# ESP32_USB_C.net
KiCad netlist of a schematic drawn in Altium Designer
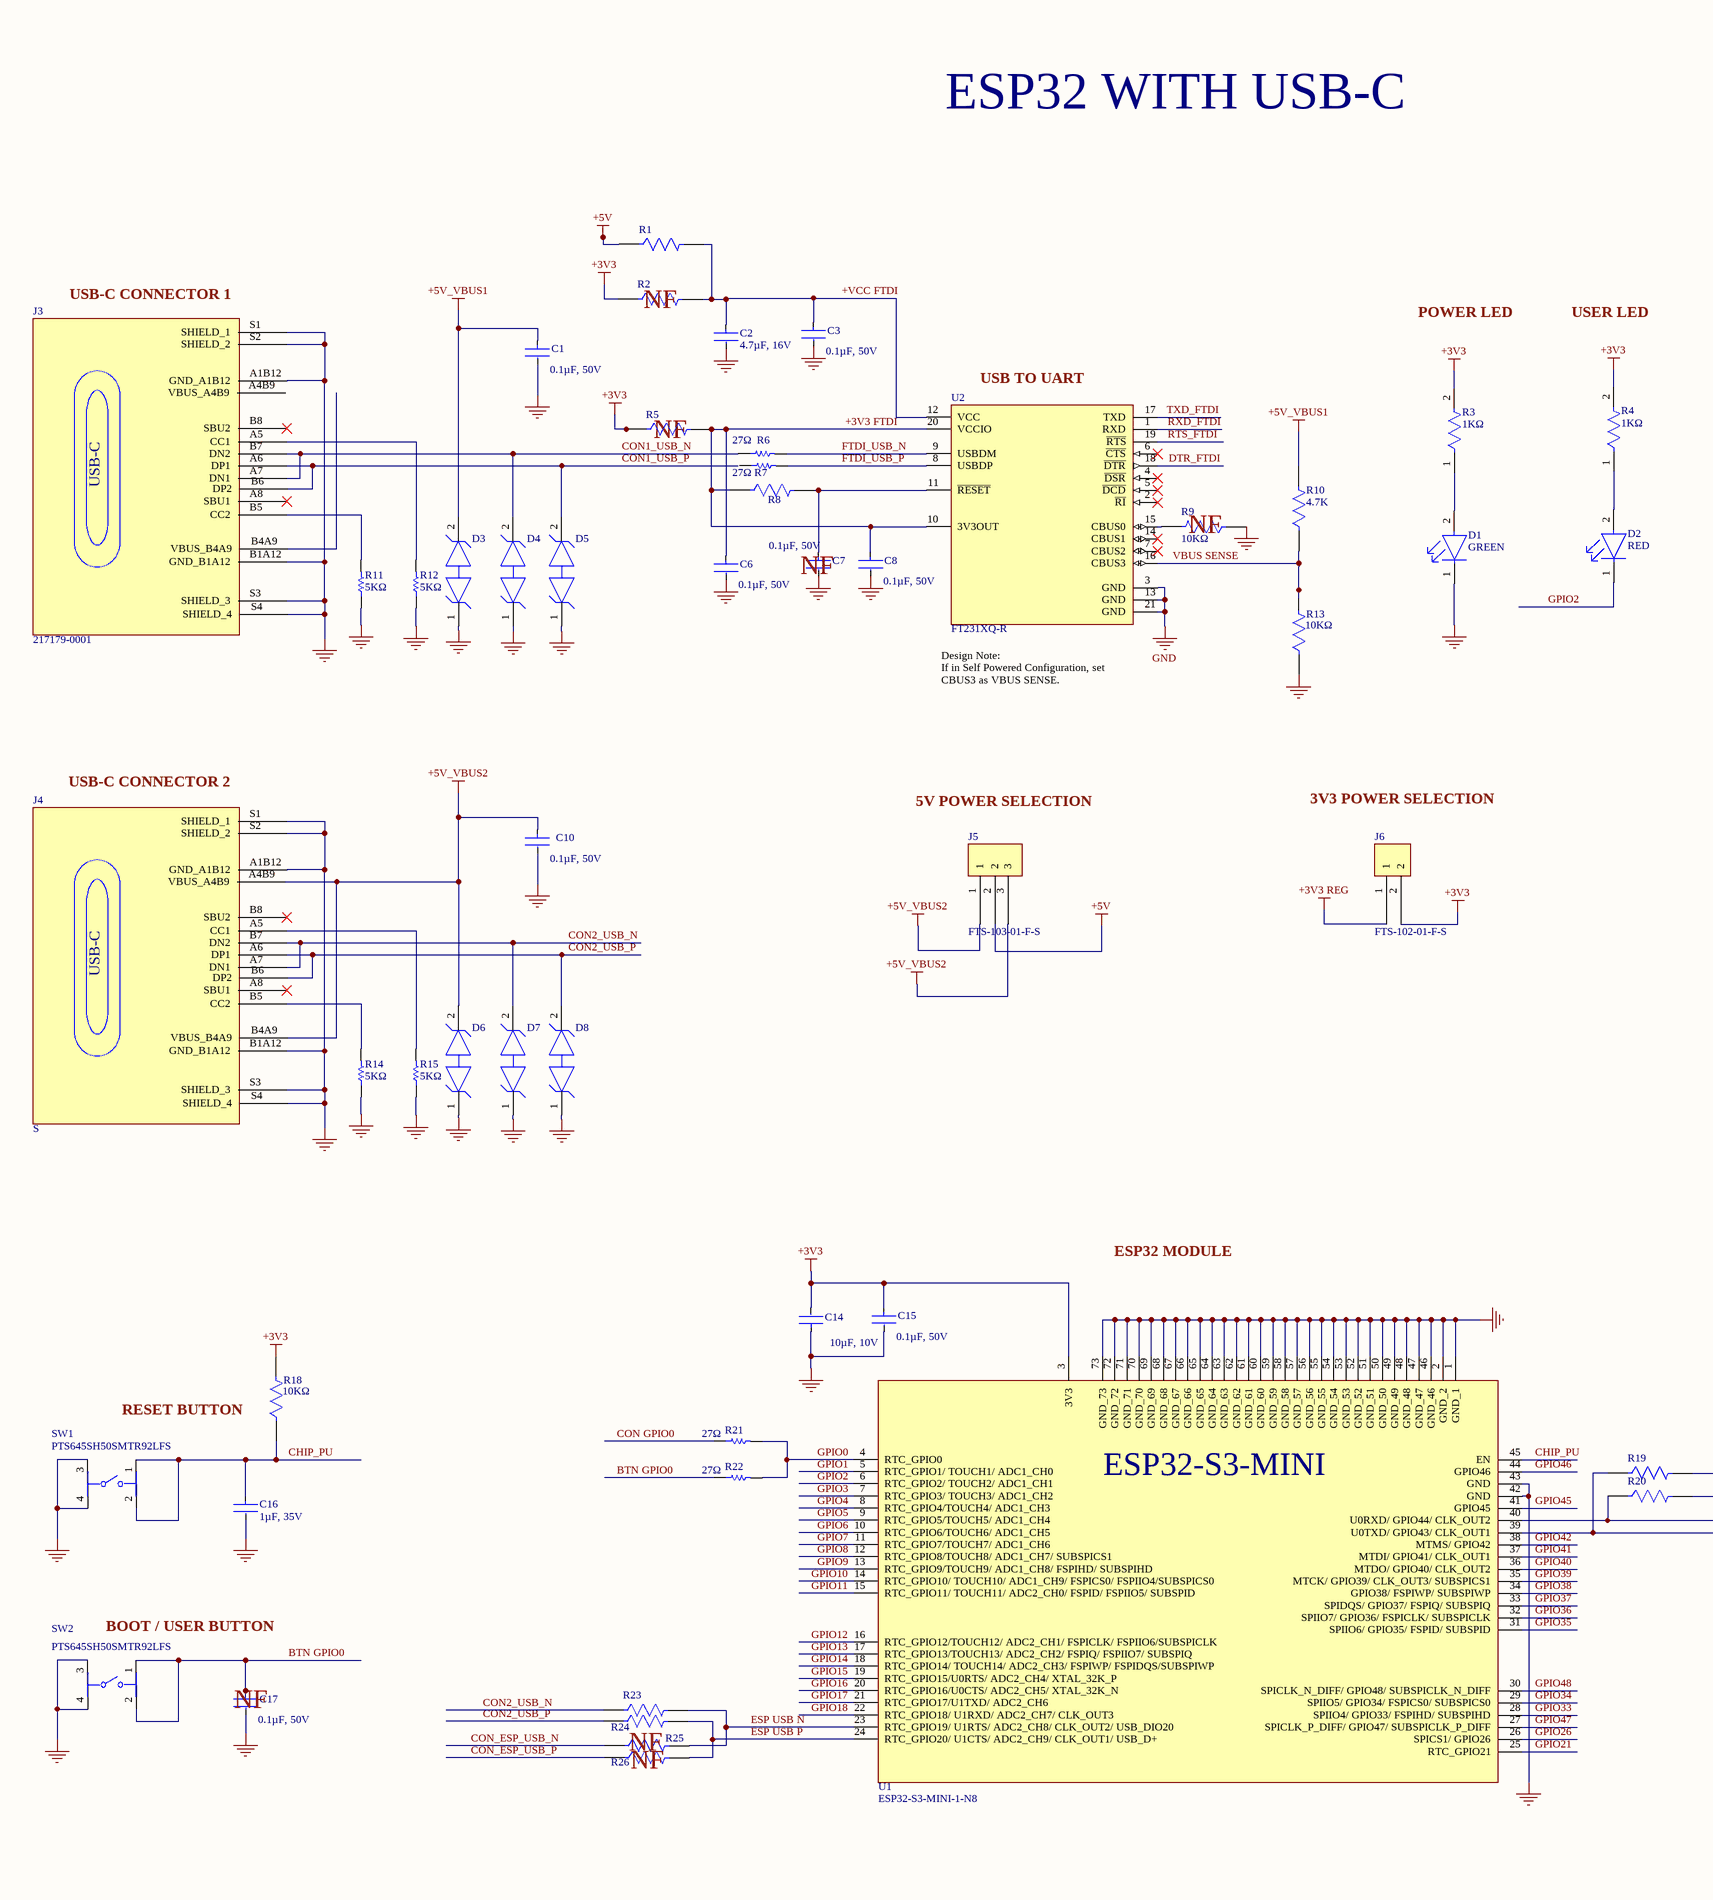
[diagram p0: ESP32_USB_C.SchDoc, left]
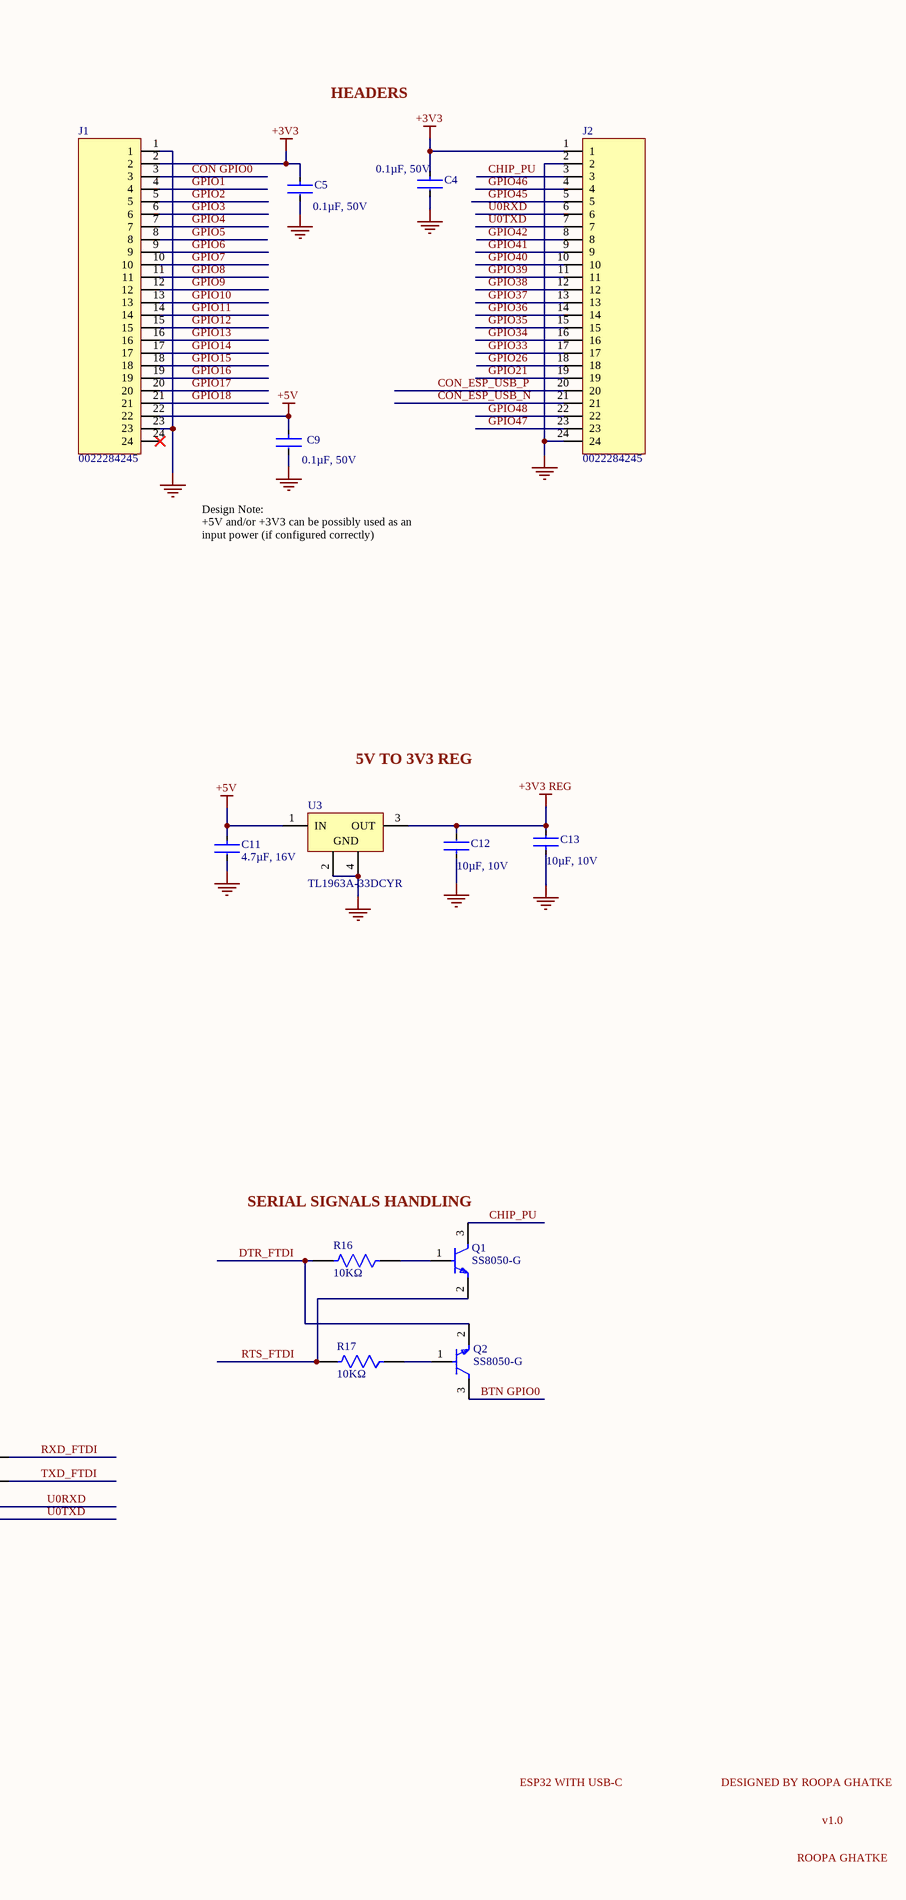
[diagram p1: ESP32_USB_C.SchDoc, right]

(export (version "E")
  (design (tool "Eeschema 10.0.6"))
  (components
    (comp (ref "C1")
      (value "0.1µF, 50V")
      (footprint "FP-CL779-IPC_C")
      (description "Cap Ceramic 100nF 50V X7R ±10% SMD 0402 +125°C Paper T/R")
      (libsource (lib "") (part "b4654b650e69147ec39a6b967a45e02_2"))
    )
    (comp (ref "C2")
      (value "4.7µF, 16V")
      (footprint "FP-CL829-IPC_C")
      (description "Cap Ceramic 4.7uF 16V X5R ±20% SMD 0402 +85°C Paper T/R")
      (fields (field (name "TOLERANCE") "20%"))
      (libsource (lib "Altium Content Vault") (part "b4654b650e69147ec39a6b967a45e02"))
    )
    (comp (ref "C3")
      (value "0.1µF, 50V")
      (footprint "FP-CL779-IPC_C")
      (description "Cap Ceramic 100nF 50V X7R ±10% SMD 0402 +125°C Paper T/R")
      (libsource (lib "Altium Content Vault") (part "b4654b650e69147ec39a6b967a45e02"))
    )
    (comp (ref "C4")
      (value "0.1µF, 50V")
      (footprint "FP-CL779-IPC_C")
      (description "Cap Ceramic 100nF 50V X7R ±10% SMD 0402 +125°C Paper T/R")
      (libsource (lib "") (part "b4654b650e69147ec39a6b967a45e02_1"))
    )
    (comp (ref "C5")
      (value "0.1µF, 50V")
      (footprint "FP-CL779-IPC_C")
      (description "Cap Ceramic 100nF 50V X7R ±10% SMD 0402 +125°C Paper T/R")
      (libsource (lib "Altium Content Vault") (part "b4654b650e69147ec39a6b967a45e02"))
    )
    (comp (ref "C6")
      (value "0.1µF, 50V")
      (footprint "FP-CL779-IPC_C")
      (description "Cap Ceramic 100nF 50V X7R ±10% SMD 0402 +125°C Paper T/R")
      (libsource (lib "Altium Content Vault") (part "b4654b650e69147ec39a6b967a45e02"))
    )
    (comp (ref "C7")
      (value "0.1µF, 50V")
      (footprint "FP-CL779-IPC_C")
      (description "Cap Ceramic 100nF 50V X7R ±10% SMD 0402 +125°C Paper T/R")
      (libsource (lib "Altium Content Vault") (part "b4654b650e69147ec39a6b967a45e02"))
    )
    (comp (ref "C8")
      (value "0.1µF, 50V")
      (footprint "FP-CL779-IPC_C")
      (description "Cap Ceramic 100nF 50V X7R ±10% SMD 0402 +125°C Paper T/R")
      (libsource (lib "Altium Content Vault") (part "b4654b650e69147ec39a6b967a45e02"))
    )
    (comp (ref "C9")
      (value "0.1µF, 50V")
      (footprint "FP-CL779-IPC_C")
      (description "Cap Ceramic 100nF 50V X7R ±10% SMD 0402 +125°C Paper T/R")
      (libsource (lib "Altium Content Vault") (part "b4654b650e69147ec39a6b967a45e02"))
    )
    (comp (ref "C10")
      (value "0.1µF, 50V")
      (footprint "FP-CL779-IPC_C")
      (description "Cap Ceramic 100nF 50V X7R ±10% SMD 0402 +125°C Paper T/R")
      (libsource (lib "Altium Content Vault") (part "b4654b650e69147ec39a6b967a45e02"))
    )
    (comp (ref "C11")
      (value "4.7µF, 16V")
      (footprint "FP-CL829-IPC_C")
      (description "Cap Ceramic 4.7uF 16V X5R ±20% SMD 0402 +85°C Paper T/R")
      (fields (field (name "TOLERANCE") "20%"))
      (libsource (lib "Altium Content Vault") (part "b4654b650e69147ec39a6b967a45e02"))
    )
    (comp (ref "C12")
      (value "10µF, 10V")
      (footprint "FP-CL07-IPC_C")
      (description "Cap Ceramic 10uF 10V X5R ±20% SMD 0402 +85°C Paper T/R")
      (fields (field (name "TOLERANCE") "20%"))
      (libsource (lib "Altium Content Vault") (part "b4654b650e69147ec39a6b967a45e02"))
    )
    (comp (ref "C13")
      (value "10µF, 10V")
      (footprint "FP-CL07-IPC_C")
      (description "Cap Ceramic 10uF 10V X5R ±20% SMD 0402 +85°C Paper T/R")
      (fields (field (name "TOLERANCE") "20%"))
      (libsource (lib "Altium Content Vault") (part "b4654b650e69147ec39a6b967a45e02"))
    )
    (comp (ref "C14")
      (value "10µF, 10V")
      (footprint "FP-CL07-IPC_C")
      (description "Cap Ceramic 10uF 10V X5R ±20% SMD 0402 +85°C Paper T/R")
      (fields (field (name "TOLERANCE") "20%"))
      (libsource (lib "Altium Content Vault") (part "b4654b650e69147ec39a6b967a45e02"))
    )
    (comp (ref "C15")
      (value "0.1µF, 50V")
      (footprint "FP-CL779-IPC_C")
      (description "Cap Ceramic 100nF 50V X7R ±10% SMD 0402 +125°C Paper T/R")
      (libsource (lib "Altium Content Vault") (part "b4654b650e69147ec39a6b967a45e02"))
    )
    (comp (ref "C16")
      (value "1µF, 35V")
      (footprint "FP-CL440-IPC_C")
      (description "Cap Ceramic 1uF 35V X5R ±10% SMD 0402 +85°C Paper T/R")
      (fields (field (name "TOLERANCE") "10%"))
      (libsource (lib "Altium Content Vault") (part "b4654b650e69147ec39a6b967a45e02"))
    )
    (comp (ref "C17")
      (value "0.1µF, 50V")
      (footprint "FP-CL779-IPC_C")
      (description "Cap Ceramic 100nF 50V X7R ±10% SMD 0402 +125°C Paper T/R")
      (libsource (lib "Altium Content Vault") (part "b4654b650e69147ec39a6b967a45e02"))
    )
    (comp (ref "D1")
      (value "GREEN")
      (footprint "FP-6_541-5056_01-4-MFG")
      (description "LED GREEN 0603 SMD")
      (fields
        (field (name "MANUFACTURER PART NUMBER") "TLMP1100-GS08")
        (field (name "MANUFACTURER") "Vishay")
      )
      (libsource (lib "Altium Content Vault") (part "8706943c75ba83719d021d2fdc84c58"))
    )
    (comp (ref "D2")
      (value "RED")
      (footprint "FP-SML-P1-MFG")
      (description "LED RED CLEAR 0402 SMD")
      (fields
        (field (name "OCTOPART") "https://octopart.com/sml-p12vtt86r-rohm-34112315")
        (field (name "MANUFACTURER") "Rohm")
      )
      (libsource (lib "Altium Content Vault") (part "8706943c75ba83719d021d2fdc84c58"))
    )
    (comp (ref "D3")
      (value "SD36C-01FTG")
      (footprint "FP-SD-C-MFG")
      (description "TVS DIODE 36V 60V SOD323")
      (fields
        (field (name "OCTOPART") "https://octopart.com/sd36c-01ftg-littelfuse-46949624")
        (field (name "MANUFACTURER") "Littelfuse")
      )
      (libsource (lib "Altium Content Vault") (part "5416617ffa6bd5ace45e61cf09a9423"))
    )
    (comp (ref "D4")
      (value "SD36C-01FTG")
      (footprint "FP-SD-C-MFG")
      (description "TVS DIODE 36V 60V SOD323")
      (fields
        (field (name "OCTOPART") "https://octopart.com/sd36c-01ftg-littelfuse-46949624")
        (field (name "MANUFACTURER") "Littelfuse")
      )
      (libsource (lib "Altium Content Vault") (part "5416617ffa6bd5ace45e61cf09a9423"))
    )
    (comp (ref "D5")
      (value "SD36C-01FTG")
      (footprint "FP-SD-C-MFG")
      (description "TVS DIODE 36V 60V SOD323")
      (fields
        (field (name "OCTOPART") "https://octopart.com/sd36c-01ftg-littelfuse-46949624")
        (field (name "MANUFACTURER") "Littelfuse")
      )
      (libsource (lib "Altium Content Vault") (part "5416617ffa6bd5ace45e61cf09a9423"))
    )
    (comp (ref "D6")
      (value "SD36C-01FTG")
      (footprint "FP-SD-C-MFG")
      (description "TVS DIODE 36V 60V SOD323")
      (fields
        (field (name "OCTOPART") "https://octopart.com/sd36c-01ftg-littelfuse-46949624")
        (field (name "MANUFACTURER") "Littelfuse")
      )
      (libsource (lib "Altium Content Vault") (part "5416617ffa6bd5ace45e61cf09a9423"))
    )
    (comp (ref "D7")
      (value "SD36C-01FTG")
      (footprint "FP-SD-C-MFG")
      (description "TVS DIODE 36V 60V SOD323")
      (fields
        (field (name "OCTOPART") "https://octopart.com/sd36c-01ftg-littelfuse-46949624")
        (field (name "MANUFACTURER") "Littelfuse")
      )
      (libsource (lib "Altium Content Vault") (part "5416617ffa6bd5ace45e61cf09a9423"))
    )
    (comp (ref "D8")
      (value "SD36C-01FTG")
      (footprint "FP-SD-C-MFG")
      (description "TVS DIODE 36V 60V SOD323")
      (fields
        (field (name "OCTOPART") "https://octopart.com/sd36c-01ftg-littelfuse-46949624")
        (field (name "MANUFACTURER") "Littelfuse")
      )
      (libsource (lib "Altium Content Vault") (part "5416617ffa6bd5ace45e61cf09a9423"))
    )
    (comp (ref "J1")
      (value "0022284245")
      (footprint "HRD_1X24_2.54MM")
      (description "CONN HEADER VERT 24POS 2.54MM")
      (fields (field (name "MANUFACTURER") "Molex") (field (name "MANUFACTURER PART NUMBER") "22-28-4245"))
      (libsource (lib "") (part "0022284245_1"))
    )
    (comp (ref "J2")
      (value "0022284245")
      (footprint "HRD_1X24_2.54MM")
      (description "CONN HEADER VERT 24POS 2.54MM")
      (fields (field (name "MANUFACTURER") "Molex") (field (name "MANUFACTURER PART NUMBER") "22-28-4245"))
      (libsource (lib "Schlib") (part "0022284245"))
    )
    (comp (ref "J3")
      (value "217179-0001")
      (footprint "MOLEX_2171790001")
      (description "USB Connector, USB Type C, USB 2.0, Receptacle, 16 Ways, Surface Mount, Through Hole Mount")
      (fields (field (name "MANUFACTURER") "Molex") (field (name "LCSC PART NUMBER") "C3197684"))
      (libsource (lib "Schlib") (part "217179-0001"))
    )
    (comp (ref "J4")
      (value "S")
      (footprint "MOLEX_2171790001")
      (description "USB Connector, USB Type C, USB 2.0, Receptacle, 16 Ways, Surface Mount, Through Hole Mount")
      (fields (field (name "MANUFACTURER") "Molex") (field (name "MANUFACTURER PART NUMBER") "217179-0001"))
      (libsource (lib "Schlib") (part "217179-0001"))
    )
    (comp (ref "J5")
      (value "FTS-103-01-F-S")
      (footprint "HRD_1X3_1.27MM")
      (description "CONN HEADER VERT 3POS 1.27MM")
      (fields (field (name "LCSC PART NUMBER") "C3333578"))
      (libsource (lib "Schlib") (part "FTS-103-01-F-S"))
    )
    (comp (ref "J6")
      (value "FTS-102-01-F-S")
      (footprint "HRD_1X2_1.27MM")
      (description "CONN HEADER VERT 2POS 1.27MM")
      (fields (field (name "LCSC PART NUMBER") "C3333578"))
      (libsource (lib "Schlib") (part "FTS-102-01-F-S"))
    )
    (comp (ref "Q1")
      (value "SS8050-G")
      (footprint "FP-SS8050-G-MFG")
      (description "NPN TRANSISTOR 1.5A 40V SOT-23 R")
      (libsource (lib "Altium Content Vault") (part "2a1388f82443b098dcd57d24ac7632d"))
    )
    (comp (ref "Q2")
      (value "SS8050-G")
      (footprint "FP-SS8050-G-MFG")
      (description "NPN TRANSISTOR 1.5A 40V SOT-23 R")
      (libsource (lib "Altium Content Vault") (part "2a1388f82443b098dcd57d24ac7632d"))
    )
    (comp (ref "R1")
      (value "RC0402FR-070RL")
      (footprint "FP-RC0402-0_4-IPC_A")
      (description "RES SMD 0 OHM JUMPER 1/16W 0402")
      (fields (field (name "TOLERANCE") "1%"))
      (libsource (lib "Altium Content Vault") (part "1029c3af85768c4190bb7ad29bc67b5"))
    )
    (comp (ref "R2")
      (value "RC0402FR-070RL")
      (footprint "FP-RC0402-0_4-IPC_A")
      (description "RES SMD 0 OHM JUMPER 1/16W 0402")
      (fields (field (name "TOLERANCE") "1%"))
      (libsource (lib "Altium Content Vault") (part "1029c3af85768c4190bb7ad29bc67b5"))
    )
    (comp (ref "R3")
      (value "1KΩ")
      (footprint "FP-RC0402-0_4-IPC_A")
      (description "RES 1K OHM 1% 1/16W 0402")
      (fields (field (name "TOLERANCE") "1%"))
      (libsource (lib "") (part "1029c3af85768c4190bb7ad29bc67b5_1"))
    )
    (comp (ref "R4")
      (value "1KΩ")
      (footprint "FP-RC0402-0_4-IPC_A")
      (description "RES 1K OHM 1% 1/16W 0402")
      (fields (field (name "TOLERANCE") "1%"))
      (libsource (lib "") (part "1029c3af85768c4190bb7ad29bc67b5_1"))
    )
    (comp (ref "R5")
      (value "RC0402FR-070RL")
      (footprint "FP-RC0402-0_4-IPC_A")
      (description "RES SMD 0 OHM JUMPER 1/16W 0402")
      (fields (field (name "TOLERANCE") "1%"))
      (libsource (lib "Altium Content Vault") (part "1029c3af85768c4190bb7ad29bc67b5"))
    )
    (comp (ref "R6")
      (value "27Ω")
      (footprint "RESC1005X40X25LL05T10")
      (fields (field (name "PART NUMBER") "RC0402FR-0727RL") (field (name "MANUFACTURER") "Yageo / Phycomp"))
      (libsource (lib "Altium Content Vault") (part "RES"))
    )
    (comp (ref "R7")
      (value "27Ω")
      (footprint "RESC1005X40X25LL05T10")
      (fields (field (name "PART NUMBER") "RC0402FR-0727RL") (field (name "MANUFACTURER") "Yageo / Phycomp"))
      (libsource (lib "Altium Content Vault") (part "RES"))
    )
    (comp (ref "R8")
      (value "RC0402FR-070RL")
      (footprint "FP-RC0402-0_4-IPC_A")
      (description "RES SMD 0 OHM JUMPER 1/16W 0402")
      (fields (field (name "TOLERANCE") "1%"))
      (libsource (lib "Altium Content Vault") (part "1029c3af85768c4190bb7ad29bc67b5"))
    )
    (comp (ref "R9")
      (value "10KΩ")
      (footprint "FP-AC0402-MFG")
      (description "RES 10kΩ ±1% 0.063W 0402")
      (fields (field (name "TOLERANCE") "1%"))
      (libsource (lib "Altium Content Vault") (part "1029c3af85768c4190bb7ad29bc67b5"))
    )
    (comp (ref "R10")
      (value "4.7K")
      (footprint "FP-RT0402-MFG")
      (description "RES SMD 4.7K OHM 0.1% 1/16W 0402")
      (fields
        (field (name "OCTOPART") "https://octopart.com/rt0402brb074k7l-yageo-71392583")
        (field (name "MANUFACTURER") "Yageo")
      )
      (libsource (lib "Altium Content Vault") (part "1029c3af85768c4190bb7ad29bc67b5"))
    )
    (comp (ref "R11")
      (value "5KΩ")
      (footprint "RESC1005X40X25NL05T10")
      (fields (field (name "PART NUMBER") "RC0402FR-075K1L") (field (name "MANUFACTURER") "Yageo / Phycomp"))
      (libsource (lib "Altium Content Vault") (part "RES"))
    )
    (comp (ref "R12")
      (value "5KΩ")
      (footprint "RESC1005X40X25NL05T10")
      (fields (field (name "PART NUMBER") "RC0402FR-075K1L") (field (name "MANUFACTURER") "Yageo / Phycomp"))
      (libsource (lib "Altium Content Vault") (part "RES"))
    )
    (comp (ref "R13")
      (value "10KΩ")
      (footprint "FP-AC0402-MFG")
      (description "RES 10kΩ ±1% 0.063W 0402")
      (fields (field (name "TOLERANCE") "1%"))
      (libsource (lib "Altium Content Vault") (part "1029c3af85768c4190bb7ad29bc67b5"))
    )
    (comp (ref "R14")
      (value "5KΩ")
      (footprint "RESC1005X40X25NL05T10")
      (fields (field (name "PART NUMBER") "RC0402FR-075K1L") (field (name "MANUFACTURER") "Yageo / Phycomp"))
      (libsource (lib "Altium Content Vault") (part "RES"))
    )
    (comp (ref "R15")
      (value "5KΩ")
      (footprint "RESC1005X40X25NL05T10")
      (fields (field (name "PART NUMBER") "RC0402FR-075K1L") (field (name "MANUFACTURER") "Yageo / Phycomp"))
      (libsource (lib "Altium Content Vault") (part "RES"))
    )
    (comp (ref "R16")
      (value "10KΩ")
      (footprint "FP-AC0402-MFG")
      (description "RES 10kΩ ±1% 0.063W 0402")
      (fields (field (name "TOLERANCE") "1%"))
      (libsource (lib "Altium Content Vault") (part "1029c3af85768c4190bb7ad29bc67b5"))
    )
    (comp (ref "R17")
      (value "10KΩ")
      (footprint "FP-AC0402-MFG")
      (description "RES 10kΩ ±1% 0.063W 0402")
      (fields (field (name "TOLERANCE") "1%"))
      (libsource (lib "Altium Content Vault") (part "1029c3af85768c4190bb7ad29bc67b5"))
    )
    (comp (ref "R18")
      (value "10KΩ")
      (footprint "FP-AC0402-MFG")
      (description "RES 10kΩ ±1% 0.063W 0402")
      (fields (field (name "TOLERANCE") "1%"))
      (libsource (lib "Altium Content Vault") (part "1029c3af85768c4190bb7ad29bc67b5"))
    )
    (comp (ref "R19")
      (value "RC0402FR-070RL")
      (footprint "FP-RC0402-0_4-IPC_A")
      (description "RES SMD 0 OHM JUMPER 1/16W 0402")
      (fields (field (name "TOLERANCE") "1%"))
      (libsource (lib "Altium Content Vault") (part "1029c3af85768c4190bb7ad29bc67b5"))
    )
    (comp (ref "R20")
      (value "RC0402FR-070RL")
      (footprint "FP-RC0402-0_4-IPC_A")
      (description "RES SMD 0 OHM JUMPER 1/16W 0402")
      (fields (field (name "TOLERANCE") "1%"))
      (libsource (lib "Altium Content Vault") (part "1029c3af85768c4190bb7ad29bc67b5"))
    )
    (comp (ref "R21")
      (value "27Ω")
      (footprint "RESC1005X40X25LL05T10")
      (fields (field (name "PART NUMBER") "RC0402FR-0727RL") (field (name "MANUFACTURER") "Yageo / Phycomp"))
      (libsource (lib "Altium Content Vault") (part "RES"))
    )
    (comp (ref "R22")
      (value "27Ω")
      (footprint "RESC1005X40X25LL05T10")
      (fields (field (name "PART NUMBER") "RC0402FR-0727RL") (field (name "MANUFACTURER") "Yageo / Phycomp"))
      (libsource (lib "Altium Content Vault") (part "RES"))
    )
    (comp (ref "R23")
      (value "RC0402FR-070RL")
      (footprint "FP-RC0402-0_4-IPC_A")
      (description "RES SMD 0 OHM JUMPER 1/16W 0402")
      (fields (field (name "TOLERANCE") "1%"))
      (libsource (lib "Altium Content Vault") (part "1029c3af85768c4190bb7ad29bc67b5"))
    )
    (comp (ref "R24")
      (value "RC0402FR-070RL")
      (footprint "FP-RC0402-0_4-IPC_A")
      (description "RES SMD 0 OHM JUMPER 1/16W 0402")
      (fields (field (name "TOLERANCE") "1%"))
      (libsource (lib "Altium Content Vault") (part "1029c3af85768c4190bb7ad29bc67b5"))
    )
    (comp (ref "R25")
      (value "RC0402FR-070RL")
      (footprint "FP-RC0402-0_4-IPC_A")
      (description "RES SMD 0 OHM JUMPER 1/16W 0402")
      (fields (field (name "TOLERANCE") "1%"))
      (libsource (lib "Altium Content Vault") (part "1029c3af85768c4190bb7ad29bc67b5"))
    )
    (comp (ref "R26")
      (value "RC0402FR-070RL")
      (footprint "FP-RC0402-0_4-IPC_A")
      (description "RES SMD 0 OHM JUMPER 1/16W 0402")
      (fields (field (name "TOLERANCE") "1%"))
      (libsource (lib "Altium Content Vault") (part "1029c3af85768c4190bb7ad29bc67b5"))
    )
    (comp (ref "SW1")
      (value "PTS645SH50SMTR92LFS")
      (footprint "FP-PTS645SH50SMTR92LFS-MFG")
      (description "SWITCH TACTILE SPST-NO 0.05A 12V")
      (libsource (lib "Altium Content Vault") (part "1adf0dd01260c80cf25a44bfd6b99ba"))
    )
    (comp (ref "SW2")
      (value "PTS645SH50SMTR92LFS")
      (footprint "FP-PTS645SH50SMTR92LFS-MFG")
      (description "SWITCH TACTILE SPST-NO 0.05A 12V")
      (libsource (lib "Altium Content Vault") (part "1adf0dd01260c80cf25a44bfd6b99ba"))
    )
    (comp (ref "U1")
      (value "ESP32-S3-MINI-1-N8")
      (footprint "XCVR_ESP32-S3-MINI-1-N8")
      (description "SMD module, ESP32-S3FN8, 8 MB SPI flash, PCB antenna")
      (fields (field (name "MANUFACTURER") "Espressif Systems") (field (name "LCSC PART NUMBER") "C2913206"))
      (libsource (lib "Schlib") (part "ESP32-S3-MINI-1-N8"))
    )
    (comp (ref "U2")
      (value "FT231XQ-R")
      (footprint "FP-QFN-20-MFG")
      (description "IC USB SERIAL FULL UART 20QFN")
      (libsource (lib "Altium Content Vault") (part "1a58eaec777a01ae16a7011961d8d4e"))
    )
    (comp (ref "U3")
      (value "TL1963A-33DCYR")
      (footprint "DCY0004A_N")
      (fields (field (name "MANUFACTURER") "Texas Instruments"))
      (libsource (lib "Altium Content Vault") (part "TI-TL1963A-XXDCY4"))
    )
  )
  (nets
    (net (code "1") (name "+3V3") (class "Default")
      (node (ref "C14") (pin "2") (pinfunction "2_2") (pintype "passive"))
      (node (ref "C15") (pin "1") (pinfunction "1_1") (pintype "passive"))
      (node (ref "C4") (pin "C4") (pinfunction "1_C4") (pintype "passive"))
      (node (ref "C5") (pin "1") (pinfunction "1_1") (pintype "passive"))
      (node (ref "J1") (pin "2") (pinfunction "2_2") (pintype "passive"))
      (node (ref "J2") (pin "1") (pinfunction "1_1") (pintype "passive"))
      (node (ref "J6") (pin "2") (pinfunction "2_2") (pintype "passive"))
      (node (ref "R18") (pin "2") (pinfunction "2_2") (pintype "passive"))
      (node (ref "R2") (pin "1") (pinfunction "1_1") (pintype "passive"))
      (node (ref "R3") (pin "2") (pinfunction "2_2") (pintype "passive"))
      (node (ref "R4") (pin "2") (pinfunction "2_2") (pintype "passive"))
      (node (ref "R5") (pin "1") (pinfunction "1_1") (pintype "passive"))
      (node (ref "U1") (pin "3") (pinfunction "3V3_3") (pintype "passive"))
    )
    (net (code "2") (name "+3V3 REG") (class "Default")
      (node (ref "C12") (pin "2") (pinfunction "2_2") (pintype "passive"))
      (node (ref "C13") (pin "2") (pinfunction "2_2") (pintype "passive"))
      (node (ref "J6") (pin "1") (pinfunction "1_1") (pintype "passive"))
      (node (ref "U3") (pin "3") (pinfunction "OUT_3") (pintype "power_in"))
    )
    (net (code "3") (name "+5V") (class "Default")
      (node (ref "C11") (pin "1") (pinfunction "1_1") (pintype "passive"))
      (node (ref "C9") (pin "1") (pinfunction "1_1") (pintype "passive"))
      (node (ref "J1") (pin "22") (pinfunction "22_22") (pintype "passive"))
      (node (ref "J5") (pin "2") (pinfunction "2_2") (pintype "passive"))
      (node (ref "R1") (pin "1") (pinfunction "1_1") (pintype "passive"))
      (node (ref "U3") (pin "1") (pinfunction "IN_1") (pintype "power_in"))
    )
    (net (code "4") (name "+5V_VBUS1") (class "Default")
      (node (ref "C1") (pin "C1") (pinfunction "1_C1") (pintype "passive"))
      (node (ref "D3") (pin "2") (pinfunction "2_2") (pintype "passive"))
      (node (ref "R10") (pin "2") (pinfunction "2_2") (pintype "passive"))
    )
    (net (code "5") (name "+5V_VBUS2") (class "Default")
      (node (ref "C10") (pin "1") (pinfunction "1_1") (pintype "passive"))
      (node (ref "D6") (pin "2") (pinfunction "2_2") (pintype "passive"))
      (node (ref "J4") (pin "A4B9") (pinfunction "VBUS_A4B9_A4B9") (pintype "passive"))
      (node (ref "J4") (pin "B4A9") (pinfunction "VBUS_B4A9_B4A9") (pintype "passive"))
      (node (ref "J5") (pin "1") (pinfunction "1_1") (pintype "passive"))
      (node (ref "J5") (pin "3") (pinfunction "3_3") (pintype "passive"))
    )
    (net (code "6") (name "/+3V3 FTDI") (class "Default")
      (node (ref "C6") (pin "1") (pinfunction "1_1") (pintype "passive"))
      (node (ref "C8") (pin "1") (pinfunction "1_1") (pintype "passive"))
      (node (ref "R5") (pin "2") (pinfunction "2_2") (pintype "passive"))
      (node (ref "R8") (pin "1") (pinfunction "1_1") (pintype "passive"))
      (node (ref "U2") (pin "10") (pinfunction "3V3OUT_10") (pintype "passive"))
      (node (ref "U2") (pin "20") (pinfunction "VCCIO_20") (pintype "power_in"))
    )
    (net (code "7") (name "/+VCC FTDI") (class "Default")
      (node (ref "C2") (pin "1") (pinfunction "1_1") (pintype "passive"))
      (node (ref "C3") (pin "1") (pinfunction "1_1") (pintype "passive"))
      (node (ref "R1") (pin "2") (pinfunction "2_2") (pintype "passive"))
      (node (ref "R2") (pin "2") (pinfunction "2_2") (pintype "passive"))
      (node (ref "U2") (pin "12") (pinfunction "VCC_12") (pintype "power_in"))
    )
    (net (code "8") (name "/BTN GPIO0") (class "Default")
      (node (ref "C17") (pin "1") (pinfunction "1_1") (pintype "passive"))
      (node (ref "Q2") (pin "3") (pinfunction "C_3") (pintype "passive"))
      (node (ref "R22") (pin "1") (pinfunction "1_1") (pintype "passive"))
      (node (ref "SW2") (pin "1") (pinfunction "1_1") (pintype "passive"))
      (node (ref "SW2") (pin "2") (pinfunction "2_2") (pintype "passive"))
    )
    (net (code "9") (name "/CHIP_PU") (class "Default")
      (node (ref "C16") (pin "1") (pinfunction "1_1") (pintype "passive"))
      (node (ref "J2") (pin "3") (pinfunction "3_3") (pintype "passive"))
      (node (ref "Q1") (pin "3") (pinfunction "C_3") (pintype "passive"))
      (node (ref "R18") (pin "1") (pinfunction "1_1") (pintype "passive"))
      (node (ref "SW1") (pin "1") (pinfunction "1_1") (pintype "passive"))
      (node (ref "SW1") (pin "2") (pinfunction "2_2") (pintype "passive"))
      (node (ref "U1") (pin "45") (pinfunction "EN_45") (pintype "passive"))
    )
    (net (code "10") (name "/CON GPIO0") (class "Default")
      (node (ref "J1") (pin "3") (pinfunction "3_3") (pintype "passive"))
      (node (ref "R21") (pin "1") (pinfunction "1_1") (pintype "passive"))
    )
    (net (code "11") (name "/CON1_USB_N") (class "Default")
      (node (ref "D4") (pin "2") (pinfunction "2_2") (pintype "passive"))
      (node (ref "J3") (pin "A7") (pinfunction "DN1_A7") (pintype "passive"))
      (node (ref "J3") (pin "B7") (pinfunction "DN2_B7") (pintype "passive"))
      (node (ref "R6") (pin "1") (pinfunction "1_1") (pintype "passive"))
    )
    (net (code "12") (name "/CON1_USB_P") (class "Default")
      (node (ref "D5") (pin "2") (pinfunction "2_2") (pintype "passive"))
      (node (ref "J3") (pin "A6") (pinfunction "DP1_A6") (pintype "passive"))
      (node (ref "J3") (pin "B6") (pinfunction "DP2_B6") (pintype "passive"))
    )
    (net (code "13") (name "/CON2_USB_N") (class "Default")
      (node (ref "D7") (pin "2") (pinfunction "2_2") (pintype "passive"))
      (node (ref "J4") (pin "A7") (pinfunction "DN1_A7") (pintype "passive"))
      (node (ref "J4") (pin "B7") (pinfunction "DN2_B7") (pintype "passive"))
      (node (ref "R23") (pin "1") (pinfunction "1_1") (pintype "passive"))
    )
    (net (code "14") (name "/CON2_USB_P") (class "Default")
      (node (ref "D8") (pin "2") (pinfunction "2_2") (pintype "passive"))
      (node (ref "J4") (pin "A6") (pinfunction "DP1_A6") (pintype "passive"))
      (node (ref "J4") (pin "B6") (pinfunction "DP2_B6") (pintype "passive"))
      (node (ref "R24") (pin "1") (pinfunction "1_1") (pintype "passive"))
    )
    (net (code "15") (name "/CON_ESP_USB_N") (class "Default")
      (node (ref "J2") (pin "21") (pinfunction "21_21") (pintype "passive"))
      (node (ref "R25") (pin "1") (pinfunction "1_1") (pintype "passive"))
    )
    (net (code "16") (name "/CON_ESP_USB_P") (class "Default")
      (node (ref "J2") (pin "20") (pinfunction "20_20") (pintype "passive"))
      (node (ref "R26") (pin "1") (pinfunction "1_1") (pintype "passive"))
    )
    (net (code "17") (name "/DTR_FTDI") (class "Default")
      (node (ref "Q2") (pin "2") (pinfunction "E_2") (pintype "passive"))
      (node (ref "R16") (pin "2") (pinfunction "2_2") (pintype "passive"))
      (node (ref "U2") (pin "18") (pinfunction "~{DTR}_18") (pintype "output"))
    )
    (net (code "18") (name "/ESP USB N") (class "Default")
      (node (ref "R23") (pin "2") (pinfunction "2_2") (pintype "passive"))
      (node (ref "R25") (pin "2") (pinfunction "2_2") (pintype "passive"))
      (node (ref "U1") (pin "23") (pinfunction "RTC_GPIO19/_U1RTS/_ADC2_CH8/_CLK_OUT2/_USB_DIO20_23") (pintype "passive"))
    )
    (net (code "19") (name "/ESP USB P") (class "Default")
      (node (ref "R24") (pin "2") (pinfunction "2_2") (pintype "passive"))
      (node (ref "R26") (pin "2") (pinfunction "2_2") (pintype "passive"))
      (node (ref "U1") (pin "24") (pinfunction "RTC_GPIO20/_U1CTS/_ADC2_CH9/_CLK_OUT1/_USB_D+_24") (pintype "passive"))
    )
    (net (code "20") (name "/FTDI_USB_N") (class "Default")
      (node (ref "R6") (pin "2") (pinfunction "2_2") (pintype "passive"))
      (node (ref "U2") (pin "9") (pinfunction "USBDM_9") (pintype "passive"))
    )
    (net (code "21") (name "/FTDI_USB_P") (class "Default")
      (node (ref "R7") (pin "2") (pinfunction "2_2") (pintype "passive"))
      (node (ref "U2") (pin "8") (pinfunction "USBDP_8") (pintype "passive"))
    )
    (net (code "22") (name "/GPIO0") (class "Default")
      (node (ref "R21") (pin "2") (pinfunction "2_2") (pintype "passive"))
      (node (ref "R22") (pin "2") (pinfunction "2_2") (pintype "passive"))
      (node (ref "U1") (pin "4") (pinfunction "RTC_GPIO0_4") (pintype "passive"))
    )
    (net (code "23") (name "/GPIO1") (class "Default")
      (node (ref "J1") (pin "4") (pinfunction "4_4") (pintype "passive"))
      (node (ref "U1") (pin "5") (pinfunction "RTC_GPIO1/_TOUCH1/_ADC1_CH0_5") (pintype "passive"))
    )
    (net (code "24") (name "/GPIO2") (class "Default")
      (node (ref "D2") (pin "1") (pinfunction "C_1") (pintype "passive"))
      (node (ref "J1") (pin "5") (pinfunction "5_5") (pintype "passive"))
      (node (ref "U1") (pin "6") (pinfunction "RTC_GPIO2/_TOUCH2/_ADC1_CH1_6") (pintype "passive"))
    )
    (net (code "25") (name "/GPIO3") (class "Default")
      (node (ref "J1") (pin "6") (pinfunction "6_6") (pintype "passive"))
      (node (ref "U1") (pin "7") (pinfunction "RTC_GPIO3/_TOUCH3/_ADC1_CH2_7") (pintype "passive"))
    )
    (net (code "26") (name "/GPIO4") (class "Default")
      (node (ref "J1") (pin "7") (pinfunction "7_7") (pintype "passive"))
      (node (ref "U1") (pin "8") (pinfunction "RTC_GPIO4/TOUCH4/_ADC1_CH3_8") (pintype "passive"))
    )
    (net (code "27") (name "/GPIO5") (class "Default")
      (node (ref "J1") (pin "8") (pinfunction "8_8") (pintype "passive"))
      (node (ref "U1") (pin "9") (pinfunction "RTC_GPIO5/TOUCH5/_ADC1_CH4_9") (pintype "passive"))
    )
    (net (code "28") (name "/GPIO6") (class "Default")
      (node (ref "J1") (pin "9") (pinfunction "9_9") (pintype "passive"))
      (node (ref "U1") (pin "10") (pinfunction "RTC_GPIO6/TOUCH6/_ADC1_CH5_10") (pintype "passive"))
    )
    (net (code "29") (name "/GPIO7") (class "Default")
      (node (ref "J1") (pin "10") (pinfunction "10_10") (pintype "passive"))
      (node (ref "U1") (pin "11") (pinfunction "RTC_GPIO7/TOUCH7/_ADC1_CH6_11") (pintype "passive"))
    )
    (net (code "30") (name "/GPIO8") (class "Default")
      (node (ref "J1") (pin "11") (pinfunction "11_11") (pintype "passive"))
      (node (ref "U1") (pin "12") (pinfunction "RTC_GPIO8/TOUCH8/_ADC1_CH7/_SUBSPICS1_12") (pintype "passive"))
    )
    (net (code "31") (name "/GPIO9") (class "Default")
      (node (ref "J1") (pin "12") (pinfunction "12_12") (pintype "passive"))
      (node (ref "U1") (pin "13") (pinfunction "RTC_GPIO9/TOUCH9/_ADC1_CH8/_FSPIHD/_SUBSPIHD_13") (pintype "passive"))
    )
    (net (code "32") (name "/GPIO10") (class "Default")
      (node (ref "J1") (pin "13") (pinfunction "13_13") (pintype "passive"))
      (node (ref "U1") (pin "14") (pinfunction "RTC_GPIO10/_TOUCH10/_ADC1_CH9/_FSPICS0/_FSPIIO4/SUBSPICS0_14") (pintype "passive"))
    )
    (net (code "33") (name "/GPIO11") (class "Default")
      (node (ref "J1") (pin "14") (pinfunction "14_14") (pintype "passive"))
      (node (ref "U1") (pin "15") (pinfunction "RTC_GPIO11/_TOUCH11/_ADC2_CH0/_FSPID/_FSPIIO5/_SUBSPID_15") (pintype "passive"))
    )
    (net (code "34") (name "/GPIO12") (class "Default")
      (node (ref "J1") (pin "15") (pinfunction "15_15") (pintype "passive"))
      (node (ref "U1") (pin "16") (pinfunction "RTC_GPIO12/TOUCH12/_ADC2_CH1/_FSPICLK/_FSPIIO6/SUBSPICLK_16") (pintype "passive"))
    )
    (net (code "35") (name "/GPIO13") (class "Default")
      (node (ref "J1") (pin "16") (pinfunction "16_16") (pintype "passive"))
      (node (ref "U1") (pin "17") (pinfunction "RTC_GPIO13/TOUCH13/_ADC2_CH2/_FSPIQ/_FSPIIO7/_SUBSPIQ_17") (pintype "passive"))
    )
    (net (code "36") (name "/GPIO14") (class "Default")
      (node (ref "J1") (pin "17") (pinfunction "17_17") (pintype "passive"))
      (node (ref "U1") (pin "18") (pinfunction "RTC_GPIO14/_TOUCH14/_ADC2_CH3/_FSPIWP/_FSPIDQS/SUBSPIWP_18") (pintype "passive"))
    )
    (net (code "37") (name "/GPIO15") (class "Default")
      (node (ref "J1") (pin "18") (pinfunction "18_18") (pintype "passive"))
      (node (ref "U1") (pin "19") (pinfunction "RTC_GPIO15/U0RTS/_ADC2_CH4/_XTAL_32K_P_19") (pintype "passive"))
    )
    (net (code "38") (name "/GPIO16") (class "Default")
      (node (ref "J1") (pin "19") (pinfunction "19_19") (pintype "passive"))
      (node (ref "U1") (pin "20") (pinfunction "RTC_GPIO16/U0CTS/_ADC2_CH5/_XTAL_32K_N_20") (pintype "passive"))
    )
    (net (code "39") (name "/GPIO17") (class "Default")
      (node (ref "J1") (pin "20") (pinfunction "20_20") (pintype "passive"))
      (node (ref "U1") (pin "21") (pinfunction "RTC_GPIO17/U1TXD/_ADC2_CH6_21") (pintype "passive"))
    )
    (net (code "40") (name "/GPIO18") (class "Default")
      (node (ref "J1") (pin "21") (pinfunction "21_21") (pintype "passive"))
      (node (ref "U1") (pin "22") (pinfunction "RTC_GPIO18/_U1RXD/_ADC2_CH7/_CLK_OUT3_22") (pintype "passive"))
    )
    (net (code "41") (name "/GPIO21") (class "Default")
      (node (ref "J2") (pin "19") (pinfunction "19_19") (pintype "passive"))
      (node (ref "U1") (pin "25") (pinfunction "RTC_GPIO21_25") (pintype "passive"))
    )
    (net (code "42") (name "/GPIO26") (class "Default")
      (node (ref "J2") (pin "18") (pinfunction "18_18") (pintype "passive"))
      (node (ref "U1") (pin "26") (pinfunction "SPICS1/_GPIO26_26") (pintype "passive"))
    )
    (net (code "43") (name "/GPIO33") (class "Default")
      (node (ref "J2") (pin "17") (pinfunction "17_17") (pintype "passive"))
      (node (ref "U1") (pin "28") (pinfunction "SPIIO4/_GPIO33/_FSPIHD/_SUBSPIHD_28") (pintype "passive"))
    )
    (net (code "44") (name "/GPIO34") (class "Default")
      (node (ref "J2") (pin "16") (pinfunction "16_16") (pintype "passive"))
      (node (ref "U1") (pin "29") (pinfunction "SPIIO5/_GPIO34/_FSPICS0/_SUBSPICS0_29") (pintype "passive"))
    )
    (net (code "45") (name "/GPIO35") (class "Default")
      (node (ref "J2") (pin "15") (pinfunction "15_15") (pintype "passive"))
      (node (ref "U1") (pin "31") (pinfunction "SPIIO6/_GPIO35/_FSPID/_SUBSPID_31") (pintype "passive"))
    )
    (net (code "46") (name "/GPIO36") (class "Default")
      (node (ref "J2") (pin "14") (pinfunction "14_14") (pintype "passive"))
      (node (ref "U1") (pin "32") (pinfunction "SPIIO7/_GPIO36/_FSPICLK/_SUBSPICLK_32") (pintype "passive"))
    )
    (net (code "47") (name "/GPIO37") (class "Default")
      (node (ref "J2") (pin "13") (pinfunction "13_13") (pintype "passive"))
      (node (ref "U1") (pin "33") (pinfunction "SPIDQS/_GPIO37/_FSPIQ/_SUBSPIQ_33") (pintype "passive"))
    )
    (net (code "48") (name "/GPIO38") (class "Default")
      (node (ref "J2") (pin "12") (pinfunction "12_12") (pintype "passive"))
      (node (ref "U1") (pin "34") (pinfunction "GPIO38/_FSPIWP/_SUBSPIWP_34") (pintype "passive"))
    )
    (net (code "49") (name "/GPIO39") (class "Default")
      (node (ref "J2") (pin "11") (pinfunction "11_11") (pintype "passive"))
      (node (ref "U1") (pin "35") (pinfunction "MTCK/_GPIO39/_CLK_OUT3/_SUBSPICS1_35") (pintype "passive"))
    )
    (net (code "50") (name "/GPIO40") (class "Default")
      (node (ref "J2") (pin "10") (pinfunction "10_10") (pintype "passive"))
      (node (ref "U1") (pin "36") (pinfunction "MTDO/_GPIO40/_CLK_OUT2_36") (pintype "passive"))
    )
    (net (code "51") (name "/GPIO41") (class "Default")
      (node (ref "J2") (pin "9") (pinfunction "9_9") (pintype "passive"))
      (node (ref "U1") (pin "37") (pinfunction "MTDI/_GPIO41/_CLK_OUT1_37") (pintype "passive"))
    )
    (net (code "52") (name "/GPIO42") (class "Default")
      (node (ref "J2") (pin "8") (pinfunction "8_8") (pintype "passive"))
      (node (ref "U1") (pin "38") (pinfunction "MTMS/_GPIO42_38") (pintype "passive"))
    )
    (net (code "53") (name "/GPIO45") (class "Default")
      (node (ref "J2") (pin "5") (pinfunction "5_5") (pintype "passive"))
      (node (ref "U1") (pin "41") (pinfunction "GPIO45_41") (pintype "passive"))
    )
    (net (code "54") (name "/GPIO46") (class "Default")
      (node (ref "J2") (pin "4") (pinfunction "4_4") (pintype "passive"))
      (node (ref "U1") (pin "44") (pinfunction "GPIO46_44") (pintype "passive"))
    )
    (net (code "55") (name "/GPIO47") (class "Default")
      (node (ref "J2") (pin "23") (pinfunction "23_23") (pintype "passive"))
      (node (ref "U1") (pin "27") (pinfunction "SPICLK_P_DIFF/_GPIO47/_SUBSPICLK_P_DIFF_27") (pintype "passive"))
    )
    (net (code "56") (name "/GPIO48") (class "Default")
      (node (ref "J2") (pin "22") (pinfunction "22_22") (pintype "passive"))
      (node (ref "U1") (pin "30") (pinfunction "SPICLK_N_DIFF/_GPIO48/_SUBSPICLK_N_DIFF_30") (pintype "passive"))
    )
    (net (code "57") (name "/RTS_FTDI") (class "Default")
      (node (ref "Q1") (pin "2") (pinfunction "E_2") (pintype "passive"))
      (node (ref "R17") (pin "2") (pinfunction "2_2") (pintype "passive"))
      (node (ref "U2") (pin "19") (pinfunction "~{RTS}_19") (pintype "passive"))
    )
    (net (code "58") (name "/RXD_FTDI") (class "Default")
      (node (ref "R19") (pin "2") (pinfunction "2_2") (pintype "passive"))
      (node (ref "U2") (pin "1") (pinfunction "RXD_1") (pintype "passive"))
    )
    (net (code "59") (name "/TXD_FTDI") (class "Default")
      (node (ref "R20") (pin "2") (pinfunction "2_2") (pintype "passive"))
      (node (ref "U2") (pin "17") (pinfunction "TXD_17") (pintype "passive"))
    )
    (net (code "60") (name "/U0RXD") (class "Default")
      (node (ref "J2") (pin "6") (pinfunction "6_6") (pintype "passive"))
      (node (ref "R20") (pin "1") (pinfunction "1_1") (pintype "passive"))
      (node (ref "U1") (pin "40") (pinfunction "U0RXD/_GPIO44/_CLK_OUT2_40") (pintype "passive"))
    )
    (net (code "61") (name "/U0TXD") (class "Default")
      (node (ref "J2") (pin "7") (pinfunction "7_7") (pintype "passive"))
      (node (ref "R19") (pin "1") (pinfunction "1_1") (pintype "passive"))
      (node (ref "U1") (pin "39") (pinfunction "U0TXD/_GPIO43/_CLK_OUT1_39") (pintype "passive"))
    )
    (net (code "62") (name "/VBUS SENSE") (class "Default")
      (node (ref "R10") (pin "1") (pinfunction "1_1") (pintype "passive"))
      (node (ref "R13") (pin "2") (pinfunction "2_2") (pintype "passive"))
      (node (ref "U2") (pin "16") (pinfunction "CBUS3_16") (pintype "bidirectional"))
    )
    (net (code "63") (name "GND") (class "Default")
      (node (ref "C1") (pin "2") (pinfunction "2_2") (pintype "passive"))
      (node (ref "C10") (pin "2") (pinfunction "2_2") (pintype "passive"))
      (node (ref "C11") (pin "2") (pinfunction "2_2") (pintype "passive"))
      (node (ref "C12") (pin "1") (pinfunction "1_1") (pintype "passive"))
      (node (ref "C13") (pin "1") (pinfunction "1_1") (pintype "passive"))
      (node (ref "C14") (pin "1") (pinfunction "1_1") (pintype "passive"))
      (node (ref "C15") (pin "2") (pinfunction "2_2") (pintype "passive"))
      (node (ref "C16") (pin "2") (pinfunction "2_2") (pintype "passive"))
      (node (ref "C17") (pin "2") (pinfunction "2_2") (pintype "passive"))
      (node (ref "C2") (pin "2") (pinfunction "2_2") (pintype "passive"))
      (node (ref "C3") (pin "2") (pinfunction "2_2") (pintype "passive"))
      (node (ref "C4") (pin "2") (pinfunction "2_2") (pintype "passive"))
      (node (ref "C5") (pin "2") (pinfunction "2_2") (pintype "passive"))
      (node (ref "C6") (pin "2") (pinfunction "2_2") (pintype "passive"))
      (node (ref "C7") (pin "2") (pinfunction "2_2") (pintype "passive"))
      (node (ref "C8") (pin "2") (pinfunction "2_2") (pintype "passive"))
      (node (ref "C9") (pin "2") (pinfunction "2_2") (pintype "passive"))
      (node (ref "D1") (pin "1") (pinfunction "C_1") (pintype "passive"))
      (node (ref "D3") (pin "1") (pinfunction "1_1") (pintype "passive"))
      (node (ref "D4") (pin "1") (pinfunction "1_1") (pintype "passive"))
      (node (ref "D5") (pin "1") (pinfunction "1_1") (pintype "passive"))
      (node (ref "D6") (pin "1") (pinfunction "1_1") (pintype "passive"))
      (node (ref "D7") (pin "1") (pinfunction "1_1") (pintype "passive"))
      (node (ref "D8") (pin "1") (pinfunction "1_1") (pintype "passive"))
      (node (ref "J1") (pin "1") (pinfunction "1_1") (pintype "passive"))
      (node (ref "J1") (pin "23") (pinfunction "23_23") (pintype "passive"))
      (node (ref "J2") (pin "2") (pinfunction "2_2") (pintype "passive"))
      (node (ref "J2") (pin "24") (pinfunction "24_24") (pintype "passive"))
      (node (ref "J3") (pin "A1B12") (pinfunction "GND_A1B12_A1B12") (pintype "passive"))
      (node (ref "J3") (pin "B1A12") (pinfunction "GND_B1A12_B1A12") (pintype "passive"))
      (node (ref "J3") (pin "S1") (pinfunction "SHIELD_1_S1") (pintype "passive"))
      (node (ref "J3") (pin "S2") (pinfunction "SHIELD_2_S2") (pintype "passive"))
      (node (ref "J3") (pin "S3") (pinfunction "SHIELD_3_S3") (pintype "passive"))
      (node (ref "J3") (pin "S4") (pinfunction "SHIELD_4_S4") (pintype "passive"))
      (node (ref "J4") (pin "A1B12") (pinfunction "GND_A1B12_A1B12") (pintype "passive"))
      (node (ref "J4") (pin "B1A12") (pinfunction "GND_B1A12_B1A12") (pintype "passive"))
      (node (ref "J4") (pin "S1") (pinfunction "SHIELD_1_S1") (pintype "passive"))
      (node (ref "J4") (pin "S2") (pinfunction "SHIELD_2_S2") (pintype "passive"))
      (node (ref "J4") (pin "S3") (pinfunction "SHIELD_3_S3") (pintype "passive"))
      (node (ref "J4") (pin "S4") (pinfunction "SHIELD_4_S4") (pintype "passive"))
      (node (ref "R11") (pin "1") (pinfunction "1_1") (pintype "passive"))
      (node (ref "R12") (pin "1") (pinfunction "1_1") (pintype "passive"))
      (node (ref "R13") (pin "1") (pinfunction "1_1") (pintype "passive"))
      (node (ref "R14") (pin "1") (pinfunction "1_1") (pintype "passive"))
      (node (ref "R15") (pin "1") (pinfunction "1_1") (pintype "passive"))
      (node (ref "R9") (pin "1") (pinfunction "1_1") (pintype "passive"))
      (node (ref "SW1") (pin "3") (pinfunction "3_3") (pintype "passive"))
      (node (ref "SW1") (pin "4") (pinfunction "4_4") (pintype "passive"))
      (node (ref "SW2") (pin "3") (pinfunction "3_3") (pintype "passive"))
      (node (ref "SW2") (pin "4") (pinfunction "4_4") (pintype "passive"))
      (node (ref "U1") (pin "1") (pinfunction "GND_1_1") (pintype "passive"))
      (node (ref "U1") (pin "2") (pinfunction "GND_2_2") (pintype "passive"))
      (node (ref "U1") (pin "42") (pinfunction "GND_42") (pintype "passive"))
      (node (ref "U1") (pin "43") (pinfunction "GND_43") (pintype "passive"))
      (node (ref "U1") (pin "46") (pinfunction "GND_46_46") (pintype "passive"))
      (node (ref "U1") (pin "47") (pinfunction "GND_47_47") (pintype "passive"))
      (node (ref "U1") (pin "48") (pinfunction "GND_48_48") (pintype "passive"))
      (node (ref "U1") (pin "49") (pinfunction "GND_49_49") (pintype "passive"))
      (node (ref "U1") (pin "50") (pinfunction "GND_50_50") (pintype "passive"))
      (node (ref "U1") (pin "51") (pinfunction "GND_51_51") (pintype "passive"))
      (node (ref "U1") (pin "52") (pinfunction "GND_52_52") (pintype "passive"))
      (node (ref "U1") (pin "53") (pinfunction "GND_53_53") (pintype "passive"))
      (node (ref "U1") (pin "54") (pinfunction "GND_54_54") (pintype "passive"))
      (node (ref "U1") (pin "55") (pinfunction "GND_55_55") (pintype "passive"))
      (node (ref "U1") (pin "56") (pinfunction "GND_56_56") (pintype "passive"))
      (node (ref "U1") (pin "57") (pinfunction "GND_57_57") (pintype "passive"))
      (node (ref "U1") (pin "58") (pinfunction "GND_58_58") (pintype "passive"))
      (node (ref "U1") (pin "59") (pinfunction "GND_59_59") (pintype "passive"))
      (node (ref "U1") (pin "60") (pinfunction "GND_60_60") (pintype "passive"))
      (node (ref "U1") (pin "61") (pinfunction "GND_61_61") (pintype "passive"))
      (node (ref "U1") (pin "62") (pinfunction "GND_62_62") (pintype "passive"))
      (node (ref "U1") (pin "63") (pinfunction "GND_63_63") (pintype "passive"))
      (node (ref "U1") (pin "64") (pinfunction "GND_64_64") (pintype "passive"))
      (node (ref "U1") (pin "65") (pinfunction "GND_65_65") (pintype "passive"))
      (node (ref "U1") (pin "66") (pinfunction "GND_66_66") (pintype "passive"))
      (node (ref "U1") (pin "67") (pinfunction "GND_67_67") (pintype "passive"))
      (node (ref "U1") (pin "68") (pinfunction "GND_68_68") (pintype "passive"))
      (node (ref "U1") (pin "69") (pinfunction "GND_69_69") (pintype "passive"))
      (node (ref "U1") (pin "70") (pinfunction "GND_70_70") (pintype "passive"))
      (node (ref "U1") (pin "71") (pinfunction "GND_71_71") (pintype "passive"))
      (node (ref "U1") (pin "72") (pinfunction "GND_72_72") (pintype "passive"))
      (node (ref "U1") (pin "73") (pinfunction "GND_73_73") (pintype "passive"))
      (node (ref "U2") (pin "13") (pinfunction "GND_13") (pintype "passive"))
      (node (ref "U2") (pin "21") (pinfunction "GND_21") (pintype "passive"))
      (node (ref "U2") (pin "3") (pinfunction "GND_3") (pintype "passive"))
      (node (ref "U3") (pin "2") (pinfunction "GND_2") (pintype "power_in"))
      (node (ref "U3") (pin "4") (pinfunction "GND_4") (pintype "power_in"))
    )
    (net (code "64") (name "Net-(D1-A)") (class "Default")
      (node (ref "D1") (pin "2") (pinfunction "A_2") (pintype "passive"))
      (node (ref "R3") (pin "1") (pinfunction "1_1") (pintype "passive"))
    )
    (net (code "65") (name "Net-(D2-A)") (class "Default")
      (node (ref "D2") (pin "2") (pinfunction "A_2") (pintype "passive"))
      (node (ref "R4") (pin "1") (pinfunction "1_1") (pintype "passive"))
    )
    (net (code "66") (name "Net-(J3-CC1)") (class "Default")
      (node (ref "J3") (pin "A5") (pinfunction "CC1_A5") (pintype "passive"))
      (node (ref "R12") (pin "2") (pinfunction "2_2") (pintype "passive"))
    )
    (net (code "67") (name "Net-(J3-CC2)") (class "Default")
      (node (ref "J3") (pin "B5") (pinfunction "CC2_B5") (pintype "passive"))
      (node (ref "R11") (pin "2") (pinfunction "2_2") (pintype "passive"))
    )
    (net (code "68") (name "Net-(J4-CC1)") (class "Default")
      (node (ref "J4") (pin "A5") (pinfunction "CC1_A5") (pintype "passive"))
      (node (ref "R15") (pin "2") (pinfunction "2_2") (pintype "passive"))
    )
    (net (code "69") (name "Net-(J4-CC2)") (class "Default")
      (node (ref "J4") (pin "B5") (pinfunction "CC2_B5") (pintype "passive"))
      (node (ref "R14") (pin "2") (pinfunction "2_2") (pintype "passive"))
    )
    (net (code "70") (name "Net-(Q1-B)") (class "Default")
      (node (ref "Q1") (pin "1") (pinfunction "B_1") (pintype "passive"))
      (node (ref "R16") (pin "1") (pinfunction "1_1") (pintype "passive"))
    )
    (net (code "71") (name "Net-(Q2-B)") (class "Default")
      (node (ref "Q2") (pin "1") (pinfunction "B_1") (pintype "passive"))
      (node (ref "R17") (pin "1") (pinfunction "1_1") (pintype "passive"))
    )
    (net (code "72") (name "Net-(U2-CBUS0)") (class "Default")
      (node (ref "R9") (pin "2") (pinfunction "2_2") (pintype "passive"))
      (node (ref "U2") (pin "15") (pinfunction "CBUS0_15") (pintype "bidirectional"))
    )
    (net (code "73") (name "Net-(U2-~{RESET})") (class "Default")
      (node (ref "C7") (pin "1") (pinfunction "1_1") (pintype "passive"))
      (node (ref "R8") (pin "2") (pinfunction "2_2") (pintype "passive"))
      (node (ref "U2") (pin "11") (pinfunction "~{RESET}_11") (pintype "passive"))
    )
    (net (code "74") (name "unconnected-(J1-Pad24)") (class "Default")
      (node (ref "J1") (pin "24") (pinfunction "24_24") (pintype "passive+no_connect"))
    )
    (net (code "75") (name "unconnected-(J3-SBU1-PadA8)") (class "Default")
      (node (ref "J3") (pin "A8") (pinfunction "SBU1_A8") (pintype "passive+no_connect"))
    )
    (net (code "76") (name "unconnected-(J3-SBU2-PadB8)") (class "Default")
      (node (ref "J3") (pin "B8") (pinfunction "SBU2_B8") (pintype "passive+no_connect"))
    )
    (net (code "77") (name "unconnected-(J3-VBUS_A4B9-PadA4B9)") (class "Default")
      (node (ref "J3") (pin "A4B9") (pinfunction "VBUS_A4B9_A4B9") (pintype "passive"))
    )
    (net (code "78") (name "unconnected-(J3-VBUS_B4A9-PadB4A9)") (class "Default")
      (node (ref "J3") (pin "B4A9") (pinfunction "VBUS_B4A9_B4A9") (pintype "passive"))
    )
    (net (code "79") (name "unconnected-(J4-SBU1-PadA8)") (class "Default")
      (node (ref "J4") (pin "A8") (pinfunction "SBU1_A8") (pintype "passive+no_connect"))
    )
    (net (code "80") (name "unconnected-(J4-SBU2-PadB8)") (class "Default")
      (node (ref "J4") (pin "B8") (pinfunction "SBU2_B8") (pintype "passive+no_connect"))
    )
    (net (code "81") (name "unconnected-(R7-Pad1)") (class "Default")
      (node (ref "R7") (pin "1") (pinfunction "1_1") (pintype "passive"))
    )
    (net (code "82") (name "unconnected-(U2-CBUS1-Pad14)") (class "Default")
      (node (ref "U2") (pin "14") (pinfunction "CBUS1_14") (pintype "bidirectional+no_connect"))
    )
    (net (code "83") (name "unconnected-(U2-CBUS2-Pad7)") (class "Default")
      (node (ref "U2") (pin "7") (pinfunction "CBUS2_7") (pintype "bidirectional+no_connect"))
    )
    (net (code "84") (name "unconnected-(U2-~{CTS}-Pad6)") (class "Default")
      (node (ref "U2") (pin "6") (pinfunction "~{CTS}_6") (pintype "input+no_connect"))
    )
    (net (code "85") (name "unconnected-(U2-~{DCD}-Pad5)") (class "Default")
      (node (ref "U2") (pin "5") (pinfunction "~{DCD}_5") (pintype "input+no_connect"))
    )
    (net (code "86") (name "unconnected-(U2-~{DSR}-Pad4)") (class "Default")
      (node (ref "U2") (pin "4") (pinfunction "~{DSR}_4") (pintype "input+no_connect"))
    )
    (net (code "87") (name "unconnected-(U2-~{RI}-Pad2)") (class "Default")
      (node (ref "U2") (pin "2") (pinfunction "~{RI}_2") (pintype "input+no_connect"))
    )
  )
)
